# CandyCaneS2.net
KiCad netlist of a schematic drawn in EasyEDA Pro
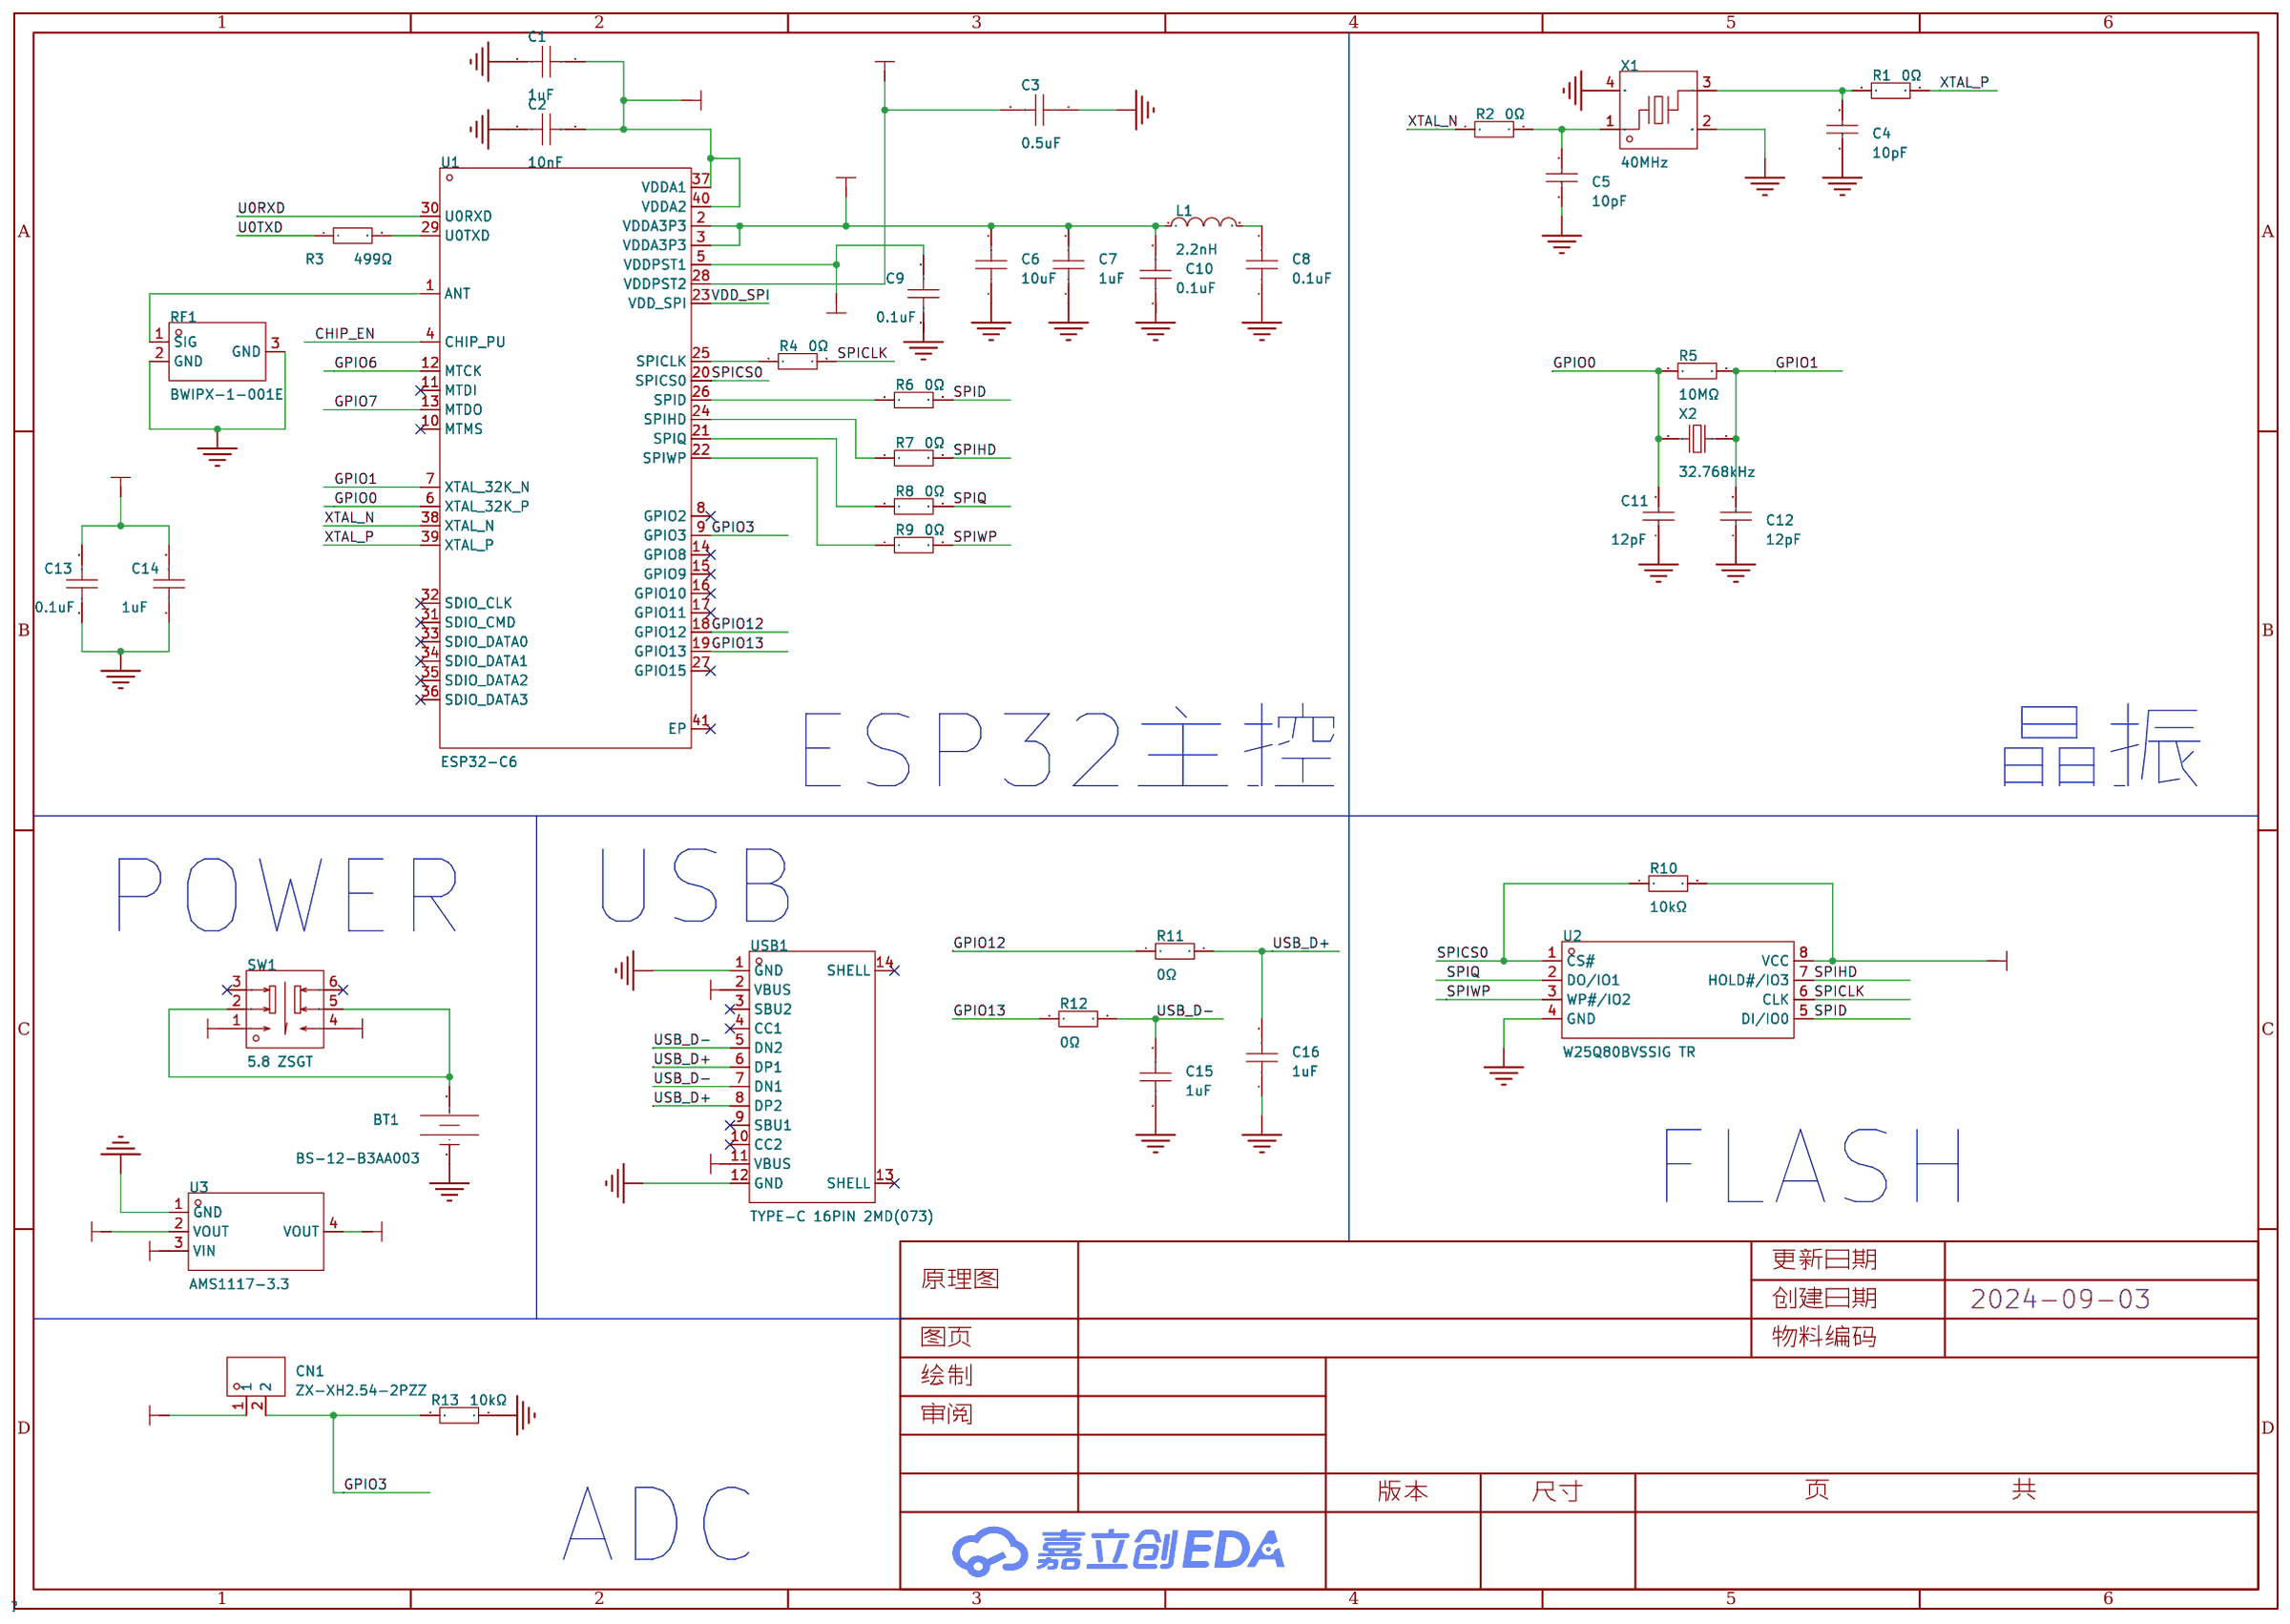
[diagram p0: P1]
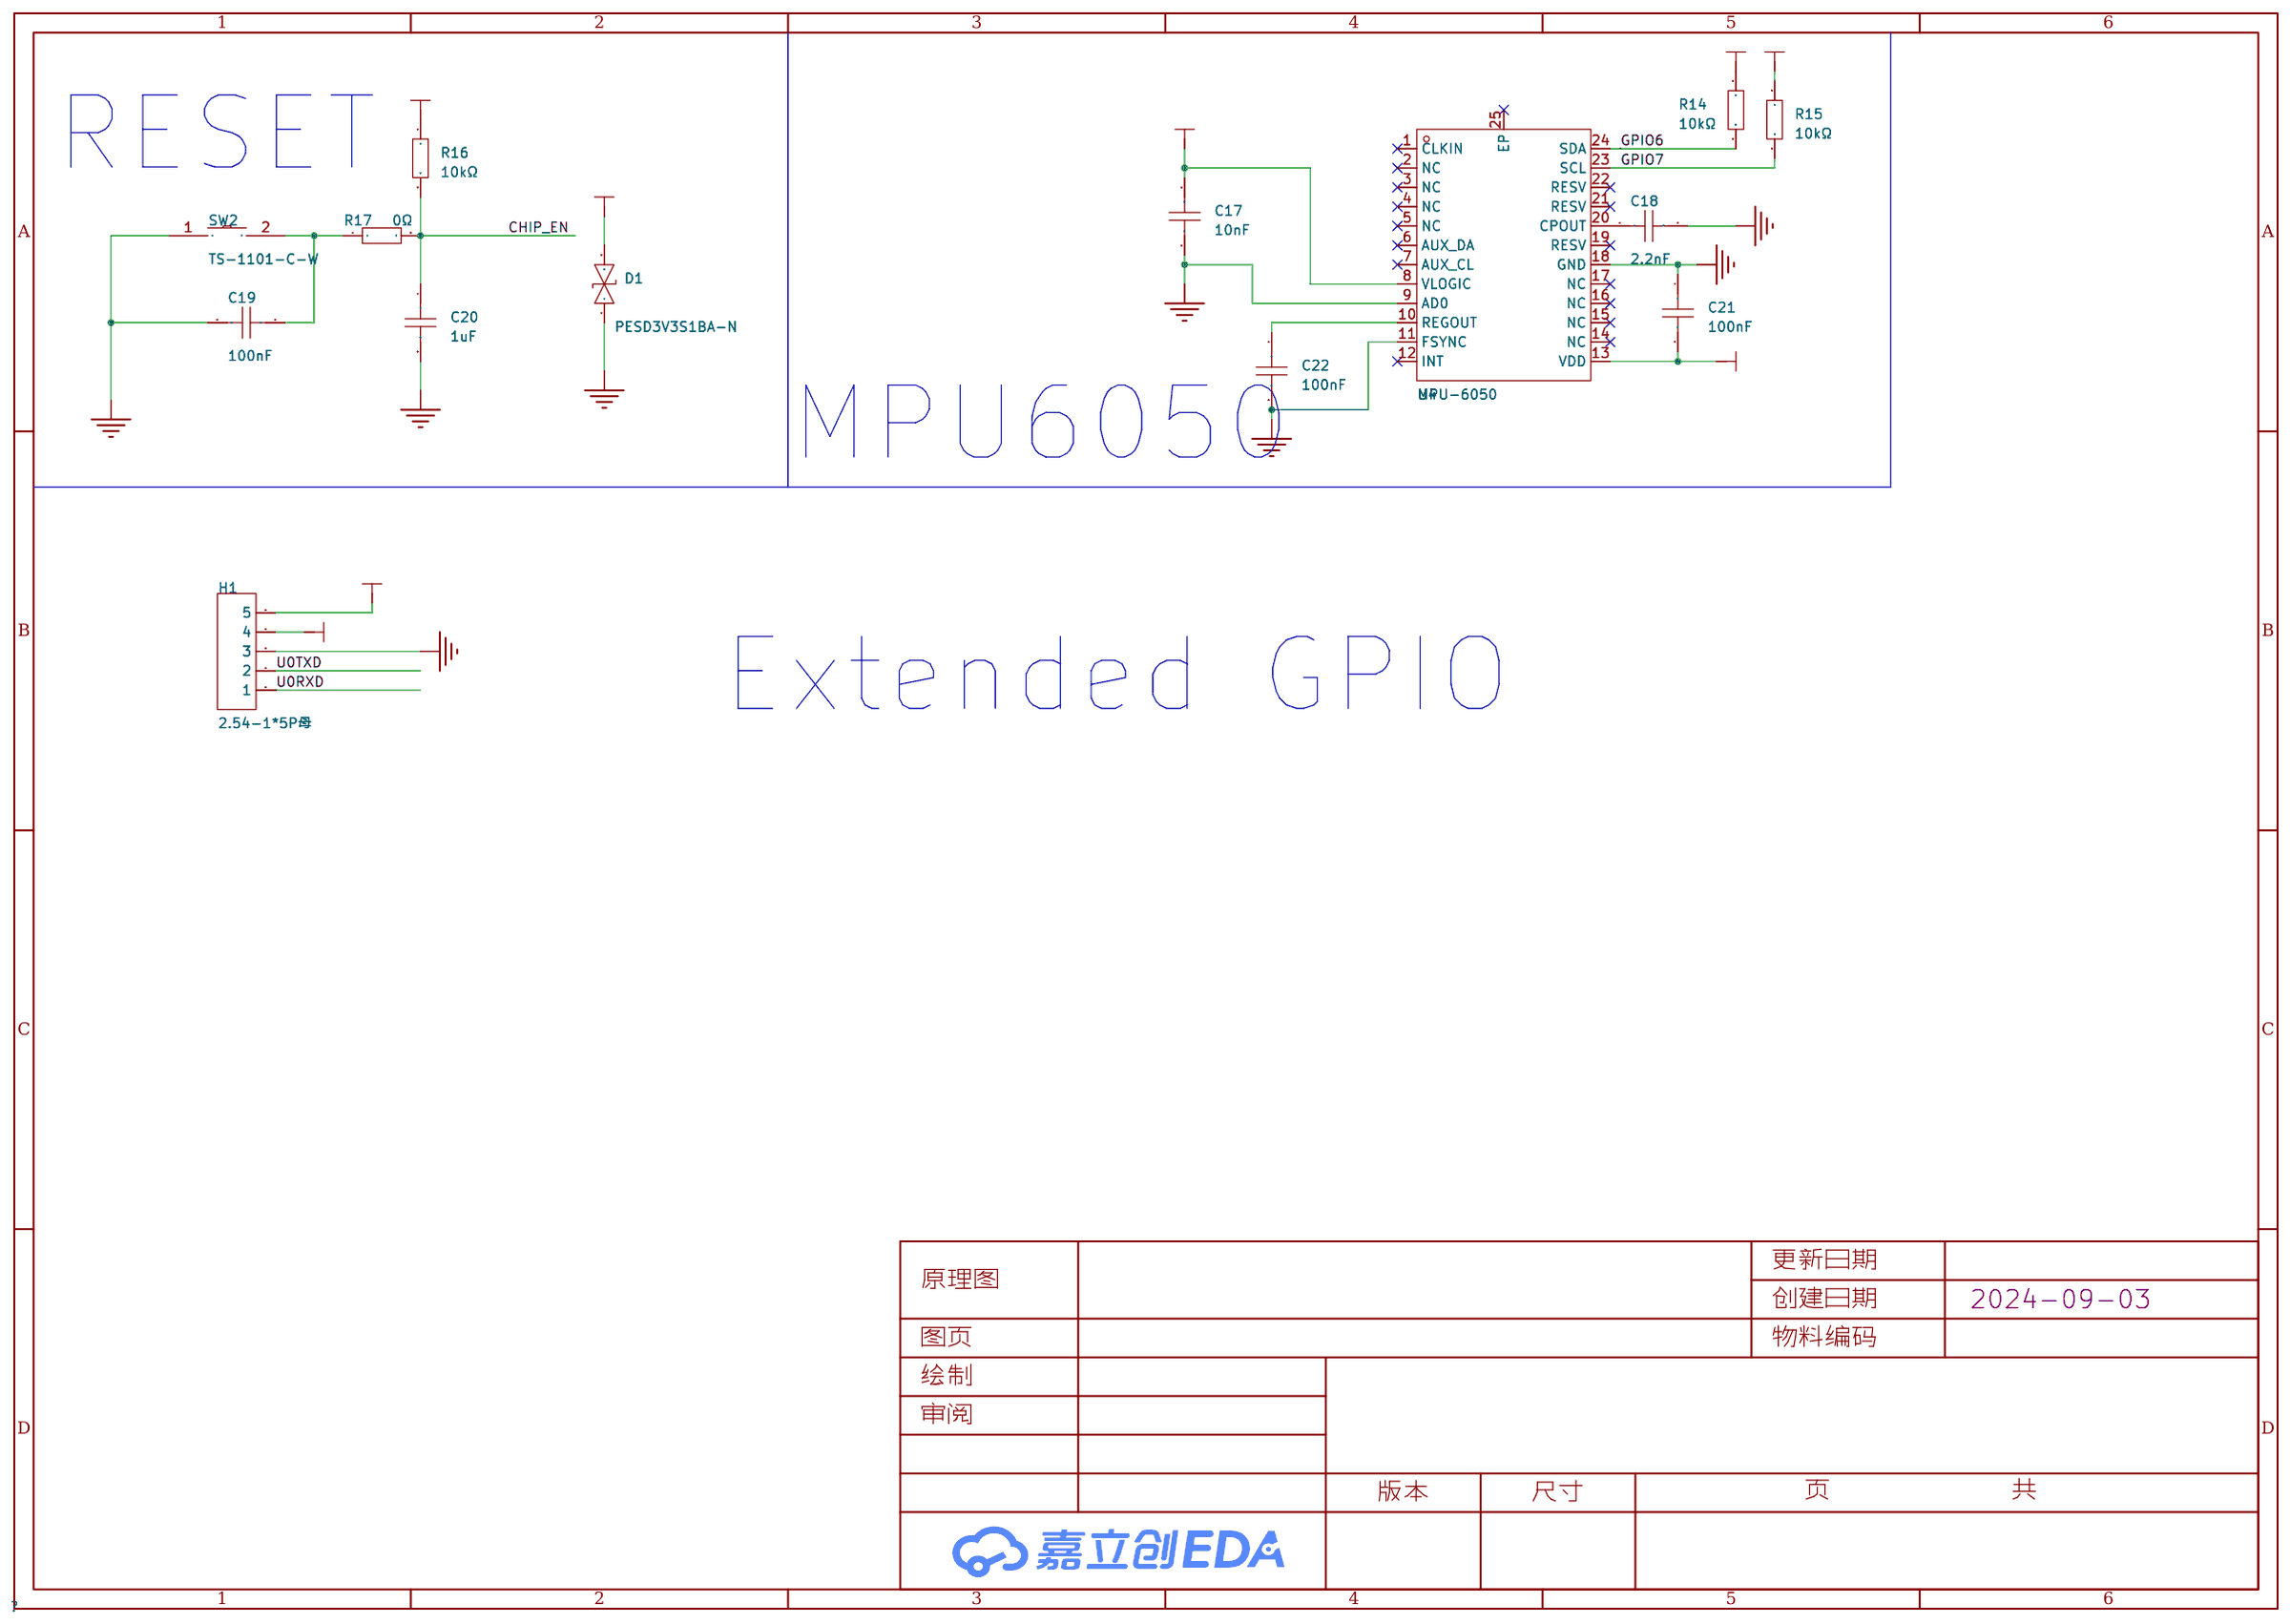
[diagram p1: P2]

(export (version "E")
  (design (tool "Eeschema 10.0.6"))
  (components
    (comp (ref "BT1")
      (value "BS-12-B3AA003")
      (footprint "easyedapro:BAT-SMD_BS-12-B3AA011")
      (description "连接器类型:电池底座;适用电池规格:CR1220;触头材质:磷青铜;工作温度范围:-25°C~+85°C;")
      (fields (field (name "Manufacturer") "MYOUNG(美阳)"))
      (libsource (lib "easyedapro") (part "BS-12-B3AA003"))
    )
    (comp (ref "C1")
      (value "1uF")
      (footprint "easyedapro:C0603")
      (description "容值:10uF;精度:±20%;额定电压:25V;材质(温度系数):X5R;")
      (fields
        (field (name "Manufacturer Part") "CL10A106MA8NRNC")
        (field (name "Manufacturer") "SAMSUNG(三星)")
      )
      (libsource (lib "easyedapro") (part "CL10A106MA8NRNC"))
    )
    (comp (ref "C2")
      (value "10nF")
      (footprint "easyedapro:C0603")
      (description "容值:10uF;精度:±20%;额定电压:25V;材质(温度系数):X5R;")
      (fields
        (field (name "Manufacturer Part") "CL10A106MA8NRNC")
        (field (name "Manufacturer") "SAMSUNG(三星)")
      )
      (libsource (lib "easyedapro") (part "CL10A106MA8NRNC"))
    )
    (comp (ref "C3")
      (value "0.5uF")
      (footprint "easyedapro:C0603")
      (description "容值:10uF;精度:±20%;额定电压:25V;材质(温度系数):X5R;")
      (fields
        (field (name "Manufacturer Part") "CL10A106MA8NRNC")
        (field (name "Manufacturer") "SAMSUNG(三星)")
      )
      (libsource (lib "easyedapro") (part "CL10A106MA8NRNC"))
    )
    (comp (ref "C4")
      (value "10pF")
      (footprint "easyedapro:C0603")
      (description "容值:10pF;精度:±5%;额定电压:50V;材质(温度系数):C0G;")
      (fields
        (field (name "Manufacturer Part") "CL10C100JB8NNNC")
        (field (name "Manufacturer") "SAMSUNG(三星)")
      )
      (libsource (lib "easyedapro") (part "CL10C100JB8NNNC"))
    )
    (comp (ref "C5")
      (value "10pF")
      (footprint "easyedapro:C0603")
      (description "容值:10pF;精度:±5%;额定电压:50V;材质(温度系数):C0G;")
      (fields
        (field (name "Manufacturer Part") "CL10C100JB8NNNC")
        (field (name "Manufacturer") "SAMSUNG(三星)")
      )
      (libsource (lib "easyedapro") (part "CL10C100JB8NNNC"))
    )
    (comp (ref "C6")
      (value "10uF")
      (footprint "easyedapro:C0603")
      (description "容值:10uF;精度:±20%;额定电压:25V;材质(温度系数):X5R;")
      (fields
        (field (name "Manufacturer Part") "CL10A106MA8NRNC")
        (field (name "Manufacturer") "SAMSUNG(三星)")
      )
      (libsource (lib "easyedapro") (part "CL10A106MA8NRNC"))
    )
    (comp (ref "C7")
      (value "1uF")
      (footprint "easyedapro:C0603")
      (description "容值:10uF;精度:±20%;额定电压:25V;材质(温度系数):X5R;")
      (fields
        (field (name "Manufacturer Part") "CL10A106MA8NRNC")
        (field (name "Manufacturer") "SAMSUNG(三星)")
      )
      (libsource (lib "easyedapro") (part "CL10A106MA8NRNC"))
    )
    (comp (ref "C8")
      (value "0.1uF")
      (footprint "easyedapro:C0603")
      (description "容值:10uF;精度:±20%;额定电压:25V;材质(温度系数):X5R;")
      (fields
        (field (name "Manufacturer Part") "CL10A106MA8NRNC")
        (field (name "Manufacturer") "SAMSUNG(三星)")
      )
      (libsource (lib "easyedapro") (part "CL10A106MA8NRNC"))
    )
    (comp (ref "C9")
      (value "0.1uF")
      (footprint "easyedapro:C0603")
      (description "容值:10uF;精度:±20%;额定电压:25V;材质(温度系数):X5R;")
      (fields
        (field (name "Manufacturer Part") "CL10A106MA8NRNC")
        (field (name "Manufacturer") "SAMSUNG(三星)")
      )
      (libsource (lib "easyedapro") (part "CL10A106MA8NRNC"))
    )
    (comp (ref "C10")
      (value "0.1uF")
      (footprint "easyedapro:C0603")
      (description "容值:10uF;精度:±20%;额定电压:25V;材质(温度系数):X5R;")
      (fields
        (field (name "Manufacturer Part") "CL10A106MA8NRNC")
        (field (name "Manufacturer") "SAMSUNG(三星)")
      )
      (libsource (lib "easyedapro") (part "CL10A106MA8NRNC"))
    )
    (comp (ref "C11")
      (value "12pF")
      (footprint "easyedapro:C0603")
      (description "容值:10pF;精度:±5%;额定电压:50V;材质(温度系数):C0G;")
      (fields
        (field (name "Manufacturer Part") "CL10C100JB8NNNC")
        (field (name "Manufacturer") "SAMSUNG(三星)")
      )
      (libsource (lib "easyedapro") (part "CL10C100JB8NNNC"))
    )
    (comp (ref "C12")
      (value "12pF")
      (footprint "easyedapro:C0603")
      (description "容值:10pF;精度:±5%;额定电压:50V;材质(温度系数):C0G;")
      (fields
        (field (name "Manufacturer Part") "CL10C100JB8NNNC")
        (field (name "Manufacturer") "SAMSUNG(三星)")
      )
      (libsource (lib "easyedapro") (part "CL10C100JB8NNNC"))
    )
    (comp (ref "C13")
      (value "0.1uF")
      (footprint "easyedapro:C0603")
      (description "容值:10uF;精度:±20%;额定电压:25V;材质(温度系数):X5R;")
      (fields
        (field (name "Manufacturer Part") "CL10A106MA8NRNC")
        (field (name "Manufacturer") "SAMSUNG(三星)")
      )
      (libsource (lib "easyedapro") (part "CL10A106MA8NRNC"))
    )
    (comp (ref "C14")
      (value "1uF")
      (footprint "easyedapro:C0603")
      (description "容值:10uF;精度:±20%;额定电压:25V;材质(温度系数):X5R;")
      (fields
        (field (name "Manufacturer Part") "CL10A106MA8NRNC")
        (field (name "Manufacturer") "SAMSUNG(三星)")
      )
      (libsource (lib "easyedapro") (part "CL10A106MA8NRNC"))
    )
    (comp (ref "C15")
      (value "1uF")
      (footprint "easyedapro:C0603")
      (description "容值:1uF;精度:±10%;额定电压:50V;材质(温度系数):X5R;")
      (fields
        (field (name "Manufacturer Part") "CL10A105KB8NNNC")
        (field (name "Manufacturer") "SAMSUNG(三星)")
      )
      (libsource (lib "easyedapro") (part "CL10A105KB8NNNC"))
    )
    (comp (ref "C16")
      (value "1uF")
      (footprint "easyedapro:C0603")
      (description "容值:1uF;精度:±10%;额定电压:50V;材质(温度系数):X5R;")
      (fields
        (field (name "Manufacturer Part") "CL10A105KB8NNNC")
        (field (name "Manufacturer") "SAMSUNG(三星)")
      )
      (libsource (lib "easyedapro") (part "CL10A105KB8NNNC"))
    )
    (comp (ref "CN1")
      (value "ZX-XH2.54-2PZZ")
      (footprint "easyedapro:CONN-TH_2P-P2.50_HX25003-2A")
      (fields (field (name "Manufacturer") "Megastar(兆星)"))
      (libsource (lib "easyedapro") (part "ZX-XH2.54-2PZZ"))
    )
    (comp (ref "L1")
      (value "2.2nH")
      (footprint "easyedapro:L0603")
      (description "电感值:2.2nH;额定电流:500mA;饱和电流(Isat):-;直流电阻(DCR):200mΩ;")
      (fields
        (field (name "Manufacturer Part") "SCC1608C2N2SSP")
        (field (name "Manufacturer") "Sunltech(韩国顺磁)")
      )
      (libsource (lib "easyedapro") (part "SCC1608C2N2SSP"))
    )
    (comp (ref "R1")
      (value "0Ω")
      (footprint "easyedapro:R0603")
      (description "电阻类型:厚膜电阻;阻值:0Ω;精度:±1%;功率:100mW;最大工作电压:75V;")
      (fields
        (field (name "Manufacturer Part") "0603WAF0000T5E")
        (field (name "Manufacturer") "UNI-ROYAL(厚声)")
      )
      (libsource (lib "easyedapro") (part "0603WAF0000T5E"))
    )
    (comp (ref "R2")
      (value "0Ω")
      (footprint "easyedapro:R0603")
      (description "电阻类型:厚膜电阻;阻值:0Ω;精度:±1%;功率:100mW;最大工作电压:75V;")
      (fields
        (field (name "Manufacturer Part") "0603WAF0000T5E")
        (field (name "Manufacturer") "UNI-ROYAL(厚声)")
      )
      (libsource (lib "easyedapro") (part "0603WAF0000T5E"))
    )
    (comp (ref "R3")
      (value "499Ω")
      (footprint "easyedapro:R0603")
      (description "电阻类型:厚膜电阻;阻值:499Ω;精度:±1%;功率:100mW;最大工作电压:75V;温度系数:±100ppm/°C;")
      (fields
        (field (name "Manufacturer Part") "0603WAF4990T5E")
        (field (name "Manufacturer") "UNI-ROYAL(厚声)")
      )
      (libsource (lib "easyedapro") (part "0603WAF4990T5E"))
    )
    (comp (ref "R4")
      (value "0Ω")
      (footprint "easyedapro:R0603")
      (description "电阻类型:厚膜电阻;阻值:0Ω;精度:±1%;功率:100mW;最大工作电压:75V;")
      (fields
        (field (name "Manufacturer Part") "0603WAF0000T5E")
        (field (name "Manufacturer") "UNI-ROYAL(厚声)")
      )
      (libsource (lib "easyedapro") (part "0603WAF0000T5E"))
    )
    (comp (ref "R5")
      (value "10MΩ")
      (footprint "easyedapro:R0603")
      (description "电阻类型:厚膜电阻;阻值:10MΩ;精度:±1%;功率:100mW;最大工作电压:75V;温度系数:±100ppm/°C;")
      (fields
        (field (name "Manufacturer Part") "0603WAF1005T5E")
        (field (name "Manufacturer") "UNI-ROYAL(厚声)")
      )
      (libsource (lib "easyedapro") (part "0603WAF1005T5E"))
    )
    (comp (ref "R6")
      (value "0Ω")
      (footprint "easyedapro:R0603")
      (description "电阻类型:厚膜电阻;阻值:0Ω;精度:±1%;功率:100mW;最大工作电压:75V;")
      (fields
        (field (name "Manufacturer Part") "0603WAF0000T5E")
        (field (name "Manufacturer") "UNI-ROYAL(厚声)")
      )
      (libsource (lib "easyedapro") (part "0603WAF0000T5E"))
    )
    (comp (ref "R7")
      (value "0Ω")
      (footprint "easyedapro:R0603")
      (description "电阻类型:厚膜电阻;阻值:0Ω;精度:±1%;功率:100mW;最大工作电压:75V;")
      (fields
        (field (name "Manufacturer Part") "0603WAF0000T5E")
        (field (name "Manufacturer") "UNI-ROYAL(厚声)")
      )
      (libsource (lib "easyedapro") (part "0603WAF0000T5E"))
    )
    (comp (ref "R8")
      (value "0Ω")
      (footprint "easyedapro:R0603")
      (description "电阻类型:厚膜电阻;阻值:0Ω;精度:±1%;功率:100mW;最大工作电压:75V;")
      (fields
        (field (name "Manufacturer Part") "0603WAF0000T5E")
        (field (name "Manufacturer") "UNI-ROYAL(厚声)")
      )
      (libsource (lib "easyedapro") (part "0603WAF0000T5E"))
    )
    (comp (ref "R9")
      (value "0Ω")
      (footprint "easyedapro:R0603")
      (description "电阻类型:厚膜电阻;阻值:0Ω;精度:±1%;功率:100mW;最大工作电压:75V;")
      (fields
        (field (name "Manufacturer Part") "0603WAF0000T5E")
        (field (name "Manufacturer") "UNI-ROYAL(厚声)")
      )
      (libsource (lib "easyedapro") (part "0603WAF0000T5E"))
    )
    (comp (ref "R10")
      (value "10kΩ")
      (footprint "easyedapro:R0603")
      (description "电阻类型:厚膜电阻;阻值:0Ω;精度:±1%;功率:100mW;最大工作电压:75V;")
      (fields
        (field (name "Manufacturer Part") "0603WAF0000T5E")
        (field (name "Manufacturer") "UNI-ROYAL(厚声)")
      )
      (libsource (lib "easyedapro") (part "0603WAF0000T5E"))
    )
    (comp (ref "R11")
      (value "0Ω")
      (footprint "easyedapro:R0603")
      (description "电阻类型:厚膜电阻;阻值:0Ω;精度:±1%;功率:100mW;最大工作电压:75V;")
      (fields
        (field (name "Manufacturer Part") "0603WAF0000T5E")
        (field (name "Manufacturer") "UNI-ROYAL(厚声)")
      )
      (libsource (lib "easyedapro") (part "0603WAF0000T5E"))
    )
    (comp (ref "R12")
      (value "0Ω")
      (footprint "easyedapro:R0603")
      (description "电阻类型:厚膜电阻;阻值:0Ω;精度:±1%;功率:100mW;最大工作电压:75V;")
      (fields
        (field (name "Manufacturer Part") "0603WAF0000T5E")
        (field (name "Manufacturer") "UNI-ROYAL(厚声)")
      )
      (libsource (lib "easyedapro") (part "0603WAF0000T5E"))
    )
    (comp (ref "R13")
      (value "10kΩ")
      (footprint "easyedapro:R0603")
      (description "电阻类型:厚膜电阻;阻值:0Ω;精度:±1%;功率:100mW;最大工作电压:75V;")
      (fields
        (field (name "Manufacturer Part") "0603WAF0000T5E")
        (field (name "Manufacturer") "UNI-ROYAL(厚声)")
      )
      (libsource (lib "easyedapro") (part "0603WAF0000T5E"))
    )
    (comp (ref "RF1")
      (value "BWIPX-1-001E")
      (footprint "easyedapro:IPEX-SMD_BWIPX-1-001E")
      (description "连接器类型:板端;接口类型:内针;端口数量:1;接口直径:-;接口长度/高度:-;频率-最大值:6GHz;射频系列:IPEX;阻抗:50Ω;样式:-;工作温度范围:-;")
      (fields (field (name "Manufacturer") "BAT WIRELESS(蝙蝠无线)"))
      (libsource (lib "easyedapro") (part "BWIPX-1-001E"))
    )
    (comp (ref "SW1")
      (value "5.8 ZSGT")
      (footprint "easyedapro:SW-TH_5.8ZSGT")
      (description "电路结构:双刀双掷;自锁/无锁:自锁;安装方式:直插;触点电流:110mA;额定电压 (DC):30V;带灯:不带;作用力:1.5N;机械寿命:10万次;")
      (fields (field (name "Manufacturer") "SHOU HAN(首韩)"))
      (libsource (lib "easyedapro") (part "5.8 ZSGT"))
    )
    (comp (ref "U1")
      (value "ESP32-C6")
      (footprint "easyedapro:QFN-40_L5.0-W5.0-P0.40-TL-EP3.3")
      (fields (field (name "Manufacturer") "ESPRESSIF(乐鑫)"))
      (libsource (lib "easyedapro") (part "ESP32-C6_C5364646"))
    )
    (comp (ref "U2")
      (value "W25Q80BVSSIG TR")
      (footprint "easyedapro:SOIC-8_L5.3-W5.3-P1.27-LS7.9-BL")
      (fields (field (name "Manufacturer") "WINBOND(华邦)"))
      (libsource (lib "easyedapro") (part "W25Q80BVSSIG TR"))
    )
    (comp (ref "U3")
      (value "AMS1117-3.3")
      (footprint "easyedapro:SOT-223-3_L6.5-W3.4-P2.30-LS7.0-BR")
      (description "输出类型:固定;最大输入电压:-;输出电压:3.3V;最大输出电流:1A;电源纹波抑制比(PSRR):72dB@(120Hz);输出极性:正极;")
      (fields (field (name "Manufacturer") "AMS"))
      (libsource (lib "easyedapro") (part "AMS1117-3.3"))
    )
    (comp (ref "USB1")
      (value "TYPE-C 16PIN 2MD(073)")
      (footprint "easyedapro:USB-C-SMD_TYPE-C-6PIN-2MD-073")
      (description "连接器类型:Type-C;标准:-;公母:母;端口数量:1;触点数量:16P;安装方式:卧贴;额定电流 - 电源:5A;工作温度范围:-25°C~+85°C;")
      (fields (field (name "Manufacturer") "SHOU HAN(首韩)"))
      (libsource (lib "easyedapro") (part "TYPE-C 16PIN 2MD(073)"))
    )
    (comp (ref "X1")
      (value "40MHz")
      (footprint "easyedapro:CRYSTAL-SMD_4P-L3.2-W2.5-BL")
      (description "晶振类型:贴片晶振;频率:40MHz;常温频差:±10ppm;外接负载电容:12pF;频率稳定度(全温):±20ppm;")
      (fields
        (field (name "Manufacturer Part") "XL2EL89COI-111YLC-40M")
        (field (name "Manufacturer") "YXC(扬兴晶振)")
      )
      (libsource (lib "easyedapro") (part "XL2EL89COI-111YLC-40M"))
    )
    (comp (ref "X2")
      (value "32.768kHz")
      (footprint "easyedapro:FC-135R_L3.2-W1.5")
      (description "晶振类型:贴片晶振;频率:32.768kHz;常温频差:±20ppm;外接负载电容:12.5pF;")
      (fields (field (name "Manufacturer Part") "Q13FC13500004") (field (name "Manufacturer") "EPSON(爱普生)"))
      (libsource (lib "easyedapro") (part "Q13FC1350000400"))
    )
    (comp (ref "C17")
      (value "10nF")
      (footprint "easyedapro:C0603")
      (description "容值:100nF;精度:±10%;额定电压:50V;材质(温度系数):X7R;")
      (fields
        (field (name "Manufacturer Part") "CL10B104KB8NNNC")
        (field (name "Manufacturer") "SAMSUNG(三星)")
      )
      (libsource (lib "easyedapro") (part "CL10B104KB8NNNC"))
    )
    (comp (ref "C18")
      (value "2.2nF")
      (footprint "easyedapro:C0603")
      (description "容值:100nF;精度:±10%;额定电压:50V;材质(温度系数):X7R;")
      (fields
        (field (name "Manufacturer Part") "CL10B104KB8NNNC")
        (field (name "Manufacturer") "SAMSUNG(三星)")
      )
      (libsource (lib "easyedapro") (part "CL10B104KB8NNNC"))
    )
    (comp (ref "C19")
      (value "100nF")
      (footprint "easyedapro:C0603")
      (description "容值:100nF;精度:±10%;额定电压:50V;材质(温度系数):X7R;")
      (fields
        (field (name "Manufacturer Part") "CL10B104KB8NNNC")
        (field (name "Manufacturer") "SAMSUNG(三星)")
      )
      (libsource (lib "easyedapro") (part "CL10B104KB8NNNC"))
    )
    (comp (ref "C20")
      (value "1uF")
      (footprint "easyedapro:C0603")
      (description "容值:100nF;精度:±10%;额定电压:50V;材质(温度系数):X7R;")
      (fields
        (field (name "Manufacturer Part") "CL10B104KB8NNNC")
        (field (name "Manufacturer") "SAMSUNG(三星)")
      )
      (libsource (lib "easyedapro") (part "CL10B104KB8NNNC"))
    )
    (comp (ref "C21")
      (value "100nF")
      (footprint "easyedapro:C0603")
      (description "容值:100nF;精度:±10%;额定电压:50V;材质(温度系数):X7R;")
      (fields
        (field (name "Manufacturer Part") "CL10B104KB8NNNC")
        (field (name "Manufacturer") "SAMSUNG(三星)")
      )
      (libsource (lib "easyedapro") (part "CL10B104KB8NNNC"))
    )
    (comp (ref "C22")
      (value "100nF")
      (footprint "easyedapro:C0603")
      (description "容值:100nF;精度:±10%;额定电压:50V;材质(温度系数):X7R;")
      (fields
        (field (name "Manufacturer Part") "CL10B104KB8NNNC")
        (field (name "Manufacturer") "SAMSUNG(三星)")
      )
      (libsource (lib "easyedapro") (part "CL10B104KB8NNNC"))
    )
    (comp (ref "D1")
      (value "PESD3V3S1BA-N")
      (footprint "easyedapro:SOD-523_L1.2-W0.8-LS1.6-BI")
      (description "反向截止电压(Vrwm):3.3V@Max;最大钳位电压:10V;峰值脉冲电流(Ipp)@10/1000us:10A@8/20us;击穿电压:4V;")
      (fields (field (name "Manufacturer") "BORN(伯恩半导体)"))
      (libsource (lib "easyedapro") (part "PESD3V3S1BA-N"))
    )
    (comp (ref "H1")
      (value "2.54-1*5P母")
      (footprint "easyedapro:HDR-TH_5P-P2.54-V-F")
      (description "插孔结构:1x5P;间距:2.54mm;行距:-;安装类型:直插;排数:单排;总孔位数:5P;塑高:-;触头材质:-;触头镀层:-;")
      (fields (field (name "Manufacturer") "BOOMELE(博穆精密)"))
      (libsource (lib "easyedapro") (part "Header-Female-2.54_1x5"))
    )
    (comp (ref "R14")
      (value "10kΩ")
      (footprint "easyedapro:R0603")
      (description "电阻类型:厚膜电阻;阻值:0Ω;精度:±1%;功率:100mW;最大工作电压:75V;")
      (fields
        (field (name "Manufacturer Part") "0603WAF0000T5E")
        (field (name "Manufacturer") "UNI-ROYAL(厚声)")
      )
      (libsource (lib "easyedapro") (part "0603WAF0000T5E"))
    )
    (comp (ref "R15")
      (value "10kΩ")
      (footprint "easyedapro:R0603")
      (description "电阻类型:厚膜电阻;阻值:0Ω;精度:±1%;功率:100mW;最大工作电压:75V;")
      (fields
        (field (name "Manufacturer Part") "0603WAF0000T5E")
        (field (name "Manufacturer") "UNI-ROYAL(厚声)")
      )
      (libsource (lib "easyedapro") (part "0603WAF0000T5E"))
    )
    (comp (ref "R16")
      (value "10kΩ")
      (footprint "easyedapro:R0603")
      (description "电阻类型:厚膜电阻;阻值:0Ω;精度:±1%;功率:100mW;最大工作电压:75V;")
      (fields
        (field (name "Manufacturer Part") "0603WAF0000T5E")
        (field (name "Manufacturer") "UNI-ROYAL(厚声)")
      )
      (libsource (lib "easyedapro") (part "0603WAF0000T5E"))
    )
    (comp (ref "R17")
      (value "0Ω")
      (footprint "easyedapro:R0603")
      (description "电阻类型:厚膜电阻;阻值:0Ω;精度:±1%;功率:100mW;最大工作电压:75V;")
      (fields
        (field (name "Manufacturer Part") "0603WAF0000T5E")
        (field (name "Manufacturer") "UNI-ROYAL(厚声)")
      )
      (libsource (lib "easyedapro") (part "0603WAF0000T5E"))
    )
    (comp (ref "SW2")
      (value "TS-1101-C-W")
      (footprint "easyedapro:SW-SMD_L6.0-W3.3-LS8.0")
      (fields (field (name "Manufacturer") "XKB Connectivity(中国星坤)"))
      (libsource (lib "easyedapro") (part "TS-1101-C-W"))
    )
    (comp (ref "U4")
      (value "MPU-6050")
      (footprint "easyedapro:QFN-24_L4.0-W4.0-P0.50-BL-EP2.7")
      (description "传感器类型:加速度计陀螺仪;")
      (fields (field (name "Manufacturer") "TDK InvenSense(应美盛)"))
      (libsource (lib "easyedapro") (part "MPU-6050_C24112"))
    )
  )
  (nets
    (net (code "1") (name "CHIP_EN") (class "Default")
      (node (ref "C20") (pin "1") (pinfunction "1_1") (pintype "unspecified"))
      (node (ref "R16") (pin "2") (pinfunction "2_2") (pintype "input"))
      (node (ref "R17") (pin "2") (pinfunction "2_2") (pintype "input"))
      (node (ref "U1") (pin "4") (pinfunction "CHIP_PU_4") (pintype "unspecified"))
    )
    (net (code "2") (name "GND") (class "Default")
      (node (ref "BT1") (pin "2") (pinfunction "-_2") (pintype "unspecified"))
      (node (ref "C1") (pin "2") (pinfunction "2_2") (pintype "unspecified"))
      (node (ref "C10") (pin "1") (pinfunction "1_1") (pintype "unspecified"))
      (node (ref "C11") (pin "1") (pinfunction "1_1") (pintype "input"))
      (node (ref "C12") (pin "1") (pinfunction "1_1") (pintype "input"))
      (node (ref "C13") (pin "1") (pinfunction "1_1") (pintype "unspecified"))
      (node (ref "C14") (pin "1") (pinfunction "1_1") (pintype "unspecified"))
      (node (ref "C15") (pin "1") (pinfunction "1_1") (pintype "unspecified"))
      (node (ref "C16") (pin "1") (pinfunction "1_1") (pintype "unspecified"))
      (node (ref "C17") (pin "2") (pinfunction "2_2") (pintype "unspecified"))
      (node (ref "C18") (pin "2") (pinfunction "2_2") (pintype "unspecified"))
      (node (ref "C19") (pin "2") (pinfunction "2_2") (pintype "unspecified"))
      (node (ref "C2") (pin "1") (pinfunction "1_1") (pintype "unspecified"))
      (node (ref "C20") (pin "2") (pinfunction "2_2") (pintype "unspecified"))
      (node (ref "C21") (pin "1") (pinfunction "1_1") (pintype "unspecified"))
      (node (ref "C22") (pin "2") (pinfunction "2_2") (pintype "unspecified"))
      (node (ref "C3") (pin "1") (pinfunction "1_1") (pintype "unspecified"))
      (node (ref "C4") (pin "1") (pinfunction "1_1") (pintype "input"))
      (node (ref "C5") (pin "1") (pinfunction "1_1") (pintype "input"))
      (node (ref "C6") (pin "1") (pinfunction "1_1") (pintype "unspecified"))
      (node (ref "C7") (pin "1") (pinfunction "1_1") (pintype "unspecified"))
      (node (ref "C8") (pin "1") (pinfunction "1_1") (pintype "unspecified"))
      (node (ref "C9") (pin "1") (pinfunction "1_1") (pintype "unspecified"))
      (node (ref "D1") (pin "1") (pinfunction "1_1") (pintype "unspecified"))
      (node (ref "H1") (pin "3") (pinfunction "3_3") (pintype "input"))
      (node (ref "R13") (pin "2") (pinfunction "2_2") (pintype "input"))
      (node (ref "RF1") (pin "2") (pinfunction "GND_2") (pintype "unspecified"))
      (node (ref "RF1") (pin "3") (pinfunction "GND_3") (pintype "unspecified"))
      (node (ref "SW2") (pin "1") (pinfunction "1_1") (pintype "unspecified"))
      (node (ref "U2") (pin "4") (pinfunction "GND_4") (pintype "unspecified"))
      (node (ref "U3") (pin "1") (pinfunction "GND_1") (pintype "unspecified"))
      (node (ref "U4") (pin "11") (pinfunction "FSYNC_11") (pintype "unspecified"))
      (node (ref "U4") (pin "18") (pinfunction "GND_18") (pintype "unspecified"))
      (node (ref "U4") (pin "9") (pinfunction "AD0_9") (pintype "unspecified"))
      (node (ref "USB1") (pin "1") (pinfunction "GND_1") (pintype "unspecified"))
      (node (ref "USB1") (pin "12") (pinfunction "GND_12") (pintype "unspecified"))
      (node (ref "X1") (pin "2") (pinfunction "GND_2") (pintype "input"))
      (node (ref "X1") (pin "4") (pinfunction "GND_4") (pintype "input"))
    )
    (net (code "3") (name "GPIO0") (class "Default")
      (node (ref "C11") (pin "2") (pinfunction "2_2") (pintype "input"))
      (node (ref "R5") (pin "1") (pinfunction "1_1") (pintype "input"))
      (node (ref "U1") (pin "6") (pinfunction "XTAL_32K_P_6") (pintype "unspecified"))
      (node (ref "X2") (pin "1") (pinfunction "1_1") (pintype "unspecified"))
    )
    (net (code "4") (name "GPIO1") (class "Default")
      (node (ref "C12") (pin "2") (pinfunction "2_2") (pintype "input"))
      (node (ref "R5") (pin "2") (pinfunction "2_2") (pintype "input"))
      (node (ref "U1") (pin "7") (pinfunction "XTAL_32K_N_7") (pintype "unspecified"))
      (node (ref "X2") (pin "2") (pinfunction "2_2") (pintype "unspecified"))
    )
    (net (code "5") (name "GPIO3") (class "Default")
      (node (ref "CN1") (pin "2") (pinfunction "2_2") (pintype "unspecified"))
      (node (ref "R13") (pin "1") (pinfunction "1_1") (pintype "input"))
      (node (ref "U1") (pin "9") (pinfunction "GPIO3_9") (pintype "unspecified"))
    )
    (net (code "6") (name "GPIO6") (class "Default")
      (node (ref "R14") (pin "2") (pinfunction "2_2") (pintype "input"))
      (node (ref "U1") (pin "12") (pinfunction "MTCK_12") (pintype "unspecified"))
      (node (ref "U4") (pin "24") (pinfunction "SDA_24") (pintype "unspecified"))
    )
    (net (code "7") (name "GPIO7") (class "Default")
      (node (ref "R15") (pin "2") (pinfunction "2_2") (pintype "input"))
      (node (ref "U1") (pin "13") (pinfunction "MTDO_13") (pintype "unspecified"))
      (node (ref "U4") (pin "23") (pinfunction "SCL_23") (pintype "unspecified"))
    )
    (net (code "8") (name "GPIO12") (class "Default")
      (node (ref "R11") (pin "1") (pinfunction "1_1") (pintype "input"))
      (node (ref "U1") (pin "18") (pinfunction "GPIO12_18") (pintype "unspecified"))
    )
    (net (code "9") (name "GPIO13") (class "Default")
      (node (ref "R12") (pin "1") (pinfunction "1_1") (pintype "input"))
      (node (ref "U1") (pin "19") (pinfunction "GPIO13_19") (pintype "unspecified"))
    )
    (net (code "10") (name "Net-(BT1-+)") (class "Default")
      (node (ref "BT1") (pin "1") (pinfunction "+_1") (pintype "unspecified"))
      (node (ref "SW1") (pin "2") (pinfunction "2_2") (pintype "unspecified"))
      (node (ref "SW1") (pin "5") (pinfunction "5_5") (pintype "unspecified"))
    )
    (net (code "11") (name "Net-(C4-Pad2)") (class "Default")
      (node (ref "C4") (pin "2") (pinfunction "2_2") (pintype "input"))
      (node (ref "R1") (pin "1") (pinfunction "1_1") (pintype "input"))
      (node (ref "X1") (pin "3") (pinfunction "3_3") (pintype "input"))
    )
    (net (code "12") (name "Net-(C5-Pad2)") (class "Default")
      (node (ref "C5") (pin "2") (pinfunction "2_2") (pintype "input"))
      (node (ref "R2") (pin "2") (pinfunction "2_2") (pintype "input"))
      (node (ref "X1") (pin "1") (pinfunction "1_1") (pintype "input"))
    )
    (net (code "13") (name "Net-(C8-Pad2)") (class "Default")
      (node (ref "C8") (pin "2") (pinfunction "2_2") (pintype "unspecified"))
      (node (ref "L1") (pin "2") (pinfunction "2_2") (pintype "unspecified"))
    )
    (net (code "14") (name "Net-(C19-Pad1)") (class "Default")
      (node (ref "C19") (pin "1") (pinfunction "1_1") (pintype "unspecified"))
      (node (ref "R17") (pin "1") (pinfunction "1_1") (pintype "input"))
      (node (ref "SW2") (pin "2") (pinfunction "2_2") (pintype "unspecified"))
    )
    (net (code "15") (name "Net-(RF1-SIG)") (class "Default")
      (node (ref "RF1") (pin "1") (pinfunction "SIG_1") (pintype "unspecified"))
      (node (ref "U1") (pin "1") (pinfunction "ANT_1") (pintype "unspecified"))
    )
    (net (code "16") (name "Net-(U1-SPICLK)") (class "Default")
      (node (ref "R4") (pin "1") (pinfunction "1_1") (pintype "input"))
      (node (ref "U1") (pin "25") (pinfunction "SPICLK_25") (pintype "unspecified"))
    )
    (net (code "17") (name "Net-(U1-SPID)") (class "Default")
      (node (ref "R6") (pin "1") (pinfunction "1_1") (pintype "input"))
      (node (ref "U1") (pin "26") (pinfunction "SPID_26") (pintype "unspecified"))
    )
    (net (code "18") (name "Net-(U1-SPIHD)") (class "Default")
      (node (ref "R7") (pin "1") (pinfunction "1_1") (pintype "input"))
      (node (ref "U1") (pin "24") (pinfunction "SPIHD_24") (pintype "unspecified"))
    )
    (net (code "19") (name "Net-(U1-SPIQ)") (class "Default")
      (node (ref "R8") (pin "1") (pinfunction "1_1") (pintype "input"))
      (node (ref "U1") (pin "21") (pinfunction "SPIQ_21") (pintype "unspecified"))
    )
    (net (code "20") (name "Net-(U1-SPIWP)") (class "Default")
      (node (ref "R9") (pin "1") (pinfunction "1_1") (pintype "input"))
      (node (ref "U1") (pin "22") (pinfunction "SPIWP_22") (pintype "unspecified"))
    )
    (net (code "21") (name "Net-(U1-U0TXD)") (class "Default")
      (node (ref "R3") (pin "2") (pinfunction "2_2") (pintype "input"))
      (node (ref "U1") (pin "29") (pinfunction "U0TXD_29") (pintype "unspecified"))
    )
    (net (code "22") (name "Net-(U4-CPOUT)") (class "Default")
      (node (ref "C18") (pin "1") (pinfunction "1_1") (pintype "unspecified"))
      (node (ref "U4") (pin "20") (pinfunction "CPOUT_20") (pintype "unspecified"))
    )
    (net (code "23") (name "Net-(U4-REGOUT)") (class "Default")
      (node (ref "C22") (pin "1") (pinfunction "1_1") (pintype "unspecified"))
      (node (ref "U4") (pin "10") (pinfunction "REGOUT_10") (pintype "unspecified"))
    )
    (net (code "24") (name "SPICLK") (class "Default")
      (node (ref "R4") (pin "2") (pinfunction "2_2") (pintype "input"))
      (node (ref "U2") (pin "6") (pinfunction "CLK_6") (pintype "unspecified"))
    )
    (net (code "25") (name "SPICS0") (class "Default")
      (node (ref "R10") (pin "1") (pinfunction "1_1") (pintype "input"))
      (node (ref "U1") (pin "20") (pinfunction "SPICS0_20") (pintype "unspecified"))
      (node (ref "U2") (pin "1") (pinfunction "CS#_1") (pintype "unspecified"))
    )
    (net (code "26") (name "SPID") (class "Default")
      (node (ref "R6") (pin "2") (pinfunction "2_2") (pintype "input"))
      (node (ref "U2") (pin "5") (pinfunction "DI/IO0_5") (pintype "unspecified"))
    )
    (net (code "27") (name "SPIHD") (class "Default")
      (node (ref "R7") (pin "2") (pinfunction "2_2") (pintype "input"))
      (node (ref "U2") (pin "7") (pinfunction "HOLD#/IO3_7") (pintype "unspecified"))
    )
    (net (code "28") (name "SPIQ") (class "Default")
      (node (ref "R8") (pin "2") (pinfunction "2_2") (pintype "input"))
      (node (ref "U2") (pin "2") (pinfunction "DO/IO1_2") (pintype "unspecified"))
    )
    (net (code "29") (name "SPIWP") (class "Default")
      (node (ref "R9") (pin "2") (pinfunction "2_2") (pintype "input"))
      (node (ref "U2") (pin "3") (pinfunction "WP#/IO2_3") (pintype "unspecified"))
    )
    (net (code "30") (name "U0RXD") (class "Default")
      (node (ref "H1") (pin "1") (pinfunction "1_1") (pintype "input"))
      (node (ref "U1") (pin "30") (pinfunction "U0RXD_30") (pintype "unspecified"))
    )
    (net (code "31") (name "U0TXD") (class "Default")
      (node (ref "H1") (pin "2") (pinfunction "2_2") (pintype "input"))
      (node (ref "R3") (pin "1") (pinfunction "1_1") (pintype "input"))
    )
    (net (code "32") (name "USB_D+") (class "Default")
      (node (ref "C16") (pin "2") (pinfunction "2_2") (pintype "unspecified"))
      (node (ref "R11") (pin "2") (pinfunction "2_2") (pintype "input"))
      (node (ref "USB1") (pin "6") (pinfunction "DP1_6") (pintype "unspecified"))
      (node (ref "USB1") (pin "8") (pinfunction "DP2_8") (pintype "unspecified"))
    )
    (net (code "33") (name "USB_D-") (class "Default")
      (node (ref "C15") (pin "2") (pinfunction "2_2") (pintype "unspecified"))
      (node (ref "R12") (pin "2") (pinfunction "2_2") (pintype "input"))
      (node (ref "USB1") (pin "5") (pinfunction "DN2_5") (pintype "unspecified"))
      (node (ref "USB1") (pin "7") (pinfunction "DN1_7") (pintype "unspecified"))
    )
    (net (code "34") (name "VBAT") (class "Default")
      (node (ref "H1") (pin "5") (pinfunction "5_5") (pintype "input"))
      (node (ref "SW1") (pin "1") (pinfunction "1_1") (pintype "unspecified"))
      (node (ref "SW1") (pin "4") (pinfunction "4_4") (pintype "unspecified"))
      (node (ref "U3") (pin "3") (pinfunction "VIN_3") (pintype "unspecified"))
      (node (ref "USB1") (pin "11") (pinfunction "VBUS_11") (pintype "unspecified"))
      (node (ref "USB1") (pin "2") (pinfunction "VBUS_2") (pintype "unspecified"))
    )
    (net (code "35") (name "VDD33") (class "Default")
      (node (ref "C1") (pin "1") (pinfunction "1_1") (pintype "unspecified"))
      (node (ref "C10") (pin "2") (pinfunction "2_2") (pintype "unspecified"))
      (node (ref "C17") (pin "1") (pinfunction "1_1") (pintype "unspecified"))
      (node (ref "C2") (pin "2") (pinfunction "2_2") (pintype "unspecified"))
      (node (ref "C21") (pin "2") (pinfunction "2_2") (pintype "unspecified"))
      (node (ref "C3") (pin "2") (pinfunction "2_2") (pintype "unspecified"))
      (node (ref "C6") (pin "2") (pinfunction "2_2") (pintype "unspecified"))
      (node (ref "C7") (pin "2") (pinfunction "2_2") (pintype "unspecified"))
      (node (ref "C9") (pin "2") (pinfunction "2_2") (pintype "unspecified"))
      (node (ref "CN1") (pin "1") (pinfunction "1_1") (pintype "unspecified"))
      (node (ref "D1") (pin "2") (pinfunction "2_2") (pintype "unspecified"))
      (node (ref "H1") (pin "4") (pinfunction "4_4") (pintype "input"))
      (node (ref "L1") (pin "1") (pinfunction "1_1") (pintype "unspecified"))
      (node (ref "R14") (pin "1") (pinfunction "1_1") (pintype "input"))
      (node (ref "R15") (pin "1") (pinfunction "1_1") (pintype "input"))
      (node (ref "R16") (pin "1") (pinfunction "1_1") (pintype "input"))
      (node (ref "U1") (pin "2") (pinfunction "VDDA3P3_2") (pintype "unspecified"))
      (node (ref "U1") (pin "28") (pinfunction "VDDPST2_28") (pintype "unspecified"))
      (node (ref "U1") (pin "3") (pinfunction "VDDA3P3_3") (pintype "unspecified"))
      (node (ref "U1") (pin "37") (pinfunction "VDDA1_37") (pintype "unspecified"))
      (node (ref "U1") (pin "40") (pinfunction "VDDA2_40") (pintype "unspecified"))
      (node (ref "U1") (pin "5") (pinfunction "VDDPST1_5") (pintype "unspecified"))
      (node (ref "U3") (pin "2") (pinfunction "VOUT_2") (pintype "unspecified"))
      (node (ref "U3") (pin "4") (pinfunction "VOUT_4") (pintype "unspecified"))
      (node (ref "U4") (pin "13") (pinfunction "VDD_13") (pintype "unspecified"))
      (node (ref "U4") (pin "8") (pinfunction "VLOGIC_8") (pintype "unspecified"))
    )
    (net (code "36") (name "VDD_SPI") (class "Default")
      (node (ref "C13") (pin "2") (pinfunction "2_2") (pintype "unspecified"))
      (node (ref "C14") (pin "2") (pinfunction "2_2") (pintype "unspecified"))
      (node (ref "R10") (pin "2") (pinfunction "2_2") (pintype "input"))
      (node (ref "U1") (pin "23") (pinfunction "VDD_SPI_23") (pintype "unspecified"))
      (node (ref "U2") (pin "8") (pinfunction "VCC_8") (pintype "unspecified"))
    )
    (net (code "37") (name "XTAL_N") (class "Default")
      (node (ref "R2") (pin "1") (pinfunction "1_1") (pintype "input"))
      (node (ref "U1") (pin "38") (pinfunction "XTAL_N_38") (pintype "unspecified"))
    )
    (net (code "38") (name "XTAL_P") (class "Default")
      (node (ref "R1") (pin "2") (pinfunction "2_2") (pintype "input"))
      (node (ref "U1") (pin "39") (pinfunction "XTAL_P_39") (pintype "unspecified"))
    )
    (net (code "39") (name "unconnected-(SW1-Pad3)") (class "Default")
      (node (ref "SW1") (pin "3") (pinfunction "3_3") (pintype "unspecified+no_connect"))
    )
    (net (code "40") (name "unconnected-(SW1-Pad6)") (class "Default")
      (node (ref "SW1") (pin "6") (pinfunction "6_6") (pintype "unspecified+no_connect"))
    )
    (net (code "41") (name "unconnected-(U1-EP-Pad41)") (class "Default")
      (node (ref "U1") (pin "41") (pinfunction "EP_41") (pintype "unspecified+no_connect"))
    )
    (net (code "42") (name "unconnected-(U1-GPIO2-Pad8)") (class "Default")
      (node (ref "U1") (pin "8") (pinfunction "GPIO2_8") (pintype "unspecified+no_connect"))
    )
    (net (code "43") (name "unconnected-(U1-GPIO8-Pad14)") (class "Default")
      (node (ref "U1") (pin "14") (pinfunction "GPIO8_14") (pintype "unspecified+no_connect"))
    )
    (net (code "44") (name "unconnected-(U1-GPIO9-Pad15)") (class "Default")
      (node (ref "U1") (pin "15") (pinfunction "GPIO9_15") (pintype "unspecified+no_connect"))
    )
    (net (code "45") (name "unconnected-(U1-GPIO10-Pad16)") (class "Default")
      (node (ref "U1") (pin "16") (pinfunction "GPIO10_16") (pintype "unspecified+no_connect"))
    )
    (net (code "46") (name "unconnected-(U1-GPIO11-Pad17)") (class "Default")
      (node (ref "U1") (pin "17") (pinfunction "GPIO11_17") (pintype "unspecified+no_connect"))
    )
    (net (code "47") (name "unconnected-(U1-GPIO15-Pad27)") (class "Default")
      (node (ref "U1") (pin "27") (pinfunction "GPIO15_27") (pintype "unspecified+no_connect"))
    )
    (net (code "48") (name "unconnected-(U1-MTDI-Pad11)") (class "Default")
      (node (ref "U1") (pin "11") (pinfunction "MTDI_11") (pintype "unspecified+no_connect"))
    )
    (net (code "49") (name "unconnected-(U1-MTMS-Pad10)") (class "Default")
      (node (ref "U1") (pin "10") (pinfunction "MTMS_10") (pintype "unspecified+no_connect"))
    )
    (net (code "50") (name "unconnected-(U1-SDIO_CLK-Pad32)") (class "Default")
      (node (ref "U1") (pin "32") (pinfunction "SDIO_CLK_32") (pintype "unspecified+no_connect"))
    )
    (net (code "51") (name "unconnected-(U1-SDIO_CMD-Pad31)") (class "Default")
      (node (ref "U1") (pin "31") (pinfunction "SDIO_CMD_31") (pintype "unspecified+no_connect"))
    )
    (net (code "52") (name "unconnected-(U1-SDIO_DATA0-Pad33)") (class "Default")
      (node (ref "U1") (pin "33") (pinfunction "SDIO_DATA0_33") (pintype "unspecified+no_connect"))
    )
    (net (code "53") (name "unconnected-(U1-SDIO_DATA1-Pad34)") (class "Default")
      (node (ref "U1") (pin "34") (pinfunction "SDIO_DATA1_34") (pintype "unspecified+no_connect"))
    )
    (net (code "54") (name "unconnected-(U1-SDIO_DATA2-Pad35)") (class "Default")
      (node (ref "U1") (pin "35") (pinfunction "SDIO_DATA2_35") (pintype "unspecified+no_connect"))
    )
    (net (code "55") (name "unconnected-(U1-SDIO_DATA3-Pad36)") (class "Default")
      (node (ref "U1") (pin "36") (pinfunction "SDIO_DATA3_36") (pintype "unspecified+no_connect"))
    )
    (net (code "56") (name "unconnected-(U4-AUX_CL-Pad7)") (class "Default")
      (node (ref "U4") (pin "7") (pinfunction "AUX_CL_7") (pintype "unspecified+no_connect"))
    )
    (net (code "57") (name "unconnected-(U4-AUX_DA-Pad6)") (class "Default")
      (node (ref "U4") (pin "6") (pinfunction "AUX_DA_6") (pintype "unspecified+no_connect"))
    )
    (net (code "58") (name "unconnected-(U4-CLKIN-Pad1)") (class "Default")
      (node (ref "U4") (pin "1") (pinfunction "CLKIN_1") (pintype "unspecified+no_connect"))
    )
    (net (code "59") (name "unconnected-(U4-EP-Pad25)") (class "Default")
      (node (ref "U4") (pin "25") (pinfunction "EP_25") (pintype "unspecified+no_connect"))
    )
    (net (code "60") (name "unconnected-(U4-INT-Pad12)") (class "Default")
      (node (ref "U4") (pin "12") (pinfunction "INT_12") (pintype "unspecified+no_connect"))
    )
    (net (code "61") (name "unconnected-(U4-NC-Pad2)") (class "Default")
      (node (ref "U4") (pin "2") (pinfunction "NC_2") (pintype "unspecified+no_connect"))
    )
    (net (code "62") (name "unconnected-(U4-NC-Pad3)") (class "Default")
      (node (ref "U4") (pin "3") (pinfunction "NC_3") (pintype "unspecified+no_connect"))
    )
    (net (code "63") (name "unconnected-(U4-NC-Pad4)") (class "Default")
      (node (ref "U4") (pin "4") (pinfunction "NC_4") (pintype "unspecified+no_connect"))
    )
    (net (code "64") (name "unconnected-(U4-NC-Pad5)") (class "Default")
      (node (ref "U4") (pin "5") (pinfunction "NC_5") (pintype "unspecified+no_connect"))
    )
    (net (code "65") (name "unconnected-(U4-NC-Pad14)") (class "Default")
      (node (ref "U4") (pin "14") (pinfunction "NC_14") (pintype "unspecified+no_connect"))
    )
    (net (code "66") (name "unconnected-(U4-NC-Pad15)") (class "Default")
      (node (ref "U4") (pin "15") (pinfunction "NC_15") (pintype "unspecified+no_connect"))
    )
    (net (code "67") (name "unconnected-(U4-NC-Pad16)") (class "Default")
      (node (ref "U4") (pin "16") (pinfunction "NC_16") (pintype "unspecified+no_connect"))
    )
    (net (code "68") (name "unconnected-(U4-NC-Pad17)") (class "Default")
      (node (ref "U4") (pin "17") (pinfunction "NC_17") (pintype "unspecified+no_connect"))
    )
    (net (code "69") (name "unconnected-(U4-RESV-Pad19)") (class "Default")
      (node (ref "U4") (pin "19") (pinfunction "RESV_19") (pintype "unspecified+no_connect"))
    )
    (net (code "70") (name "unconnected-(U4-RESV-Pad21)") (class "Default")
      (node (ref "U4") (pin "21") (pinfunction "RESV_21") (pintype "unspecified+no_connect"))
    )
    (net (code "71") (name "unconnected-(U4-RESV-Pad22)") (class "Default")
      (node (ref "U4") (pin "22") (pinfunction "RESV_22") (pintype "unspecified+no_connect"))
    )
    (net (code "72") (name "unconnected-(USB1-CC1-Pad4)") (class "Default")
      (node (ref "USB1") (pin "4") (pinfunction "CC1_4") (pintype "unspecified+no_connect"))
    )
    (net (code "73") (name "unconnected-(USB1-CC2-Pad10)") (class "Default")
      (node (ref "USB1") (pin "10") (pinfunction "CC2_10") (pintype "unspecified+no_connect"))
    )
    (net (code "74") (name "unconnected-(USB1-SBU1-Pad9)") (class "Default")
      (node (ref "USB1") (pin "9") (pinfunction "SBU1_9") (pintype "unspecified+no_connect"))
    )
    (net (code "75") (name "unconnected-(USB1-SBU2-Pad3)") (class "Default")
      (node (ref "USB1") (pin "3") (pinfunction "SBU2_3") (pintype "unspecified+no_connect"))
    )
    (net (code "76") (name "unconnected-(USB1-SHELL-Pad13)") (class "Default")
      (node (ref "USB1") (pin "13") (pinfunction "SHELL_13") (pintype "unspecified+no_connect"))
    )
    (net (code "77") (name "unconnected-(USB1-SHELL-Pad14)") (class "Default")
      (node (ref "USB1") (pin "14") (pinfunction "SHELL_14") (pintype "unspecified+no_connect"))
    )
  )
)
